# Fireplace_Control.net
KiCad netlist of a schematic drawn in EAGLE
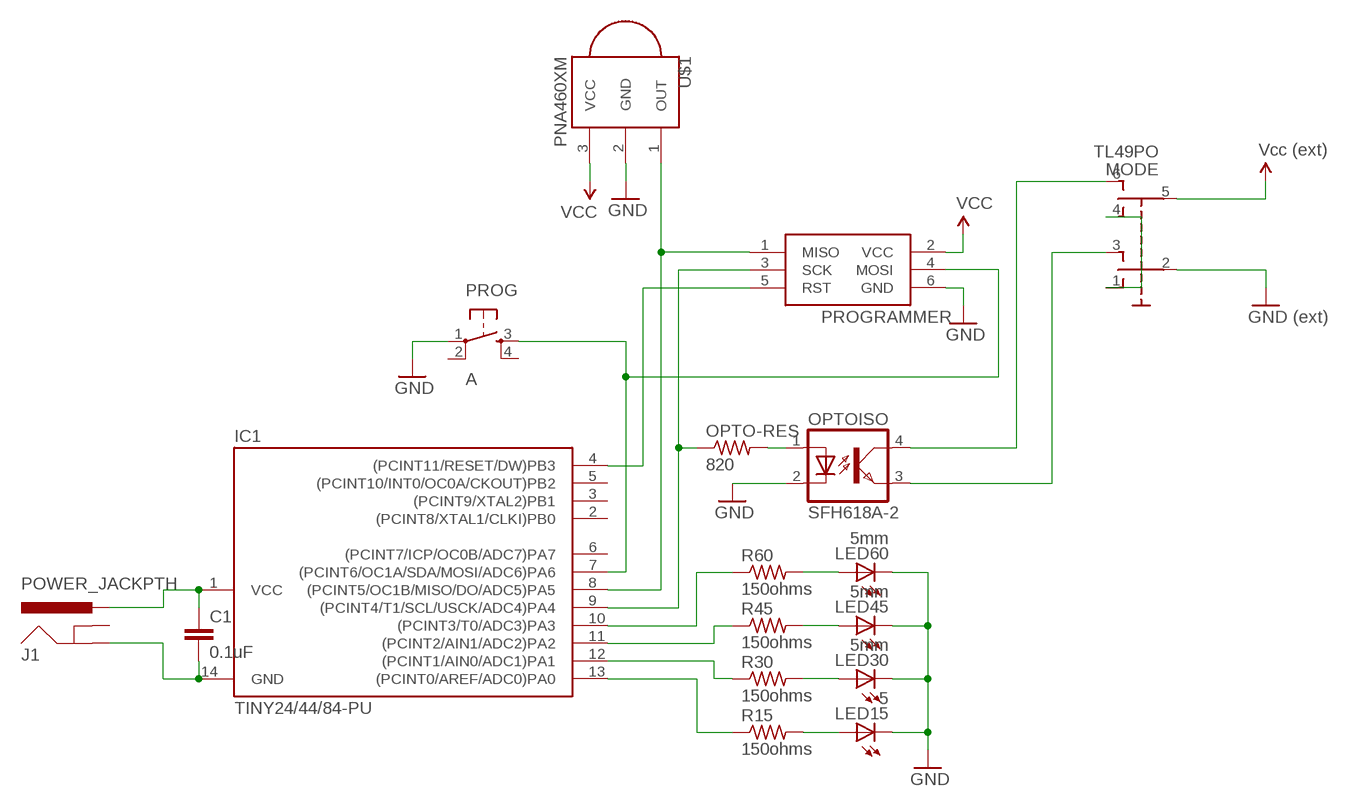
[diagram p0: schematic, sheet 1]

(export (version "E")
  (design (tool "Eeschema 10.0.6"))
  (components
    (comp (ref "C1")
      (value "0.1uF")
      (footprint "eagle-import:CAP-PTH-SMALL-KIT")
      (libsource (lib "eagle-import") (part "CAPKIT"))
    )
    (comp (ref "IC1")
      (value "TINY24/44/84-PU")
      (footprint "eagle-import:DIL14")
      (libsource (lib "eagle-import") (part "TINY24/44/84-PU"))
    )
    (comp (ref "J1")
      (value "POWER_JACKPTH")
      (footprint "eagle-import:POWER_JACK_PTH")
      (libsource (lib "eagle-import") (part "POWER_JACKPTH"))
    )
    (comp (ref "LED15")
      (value "5")
      (footprint "eagle-import:LED3MM")
      (libsource (lib "eagle-import") (part "LED3MM"))
    )
    (comp (ref "LED30")
      (value "5mm")
      (footprint "eagle-import:LED3MM")
      (libsource (lib "eagle-import") (part "LED3MM"))
    )
    (comp (ref "LED45")
      (value "5mm")
      (footprint "eagle-import:LED3MM")
      (libsource (lib "eagle-import") (part "LED3MM"))
    )
    (comp (ref "LED60")
      (value "5mm")
      (footprint "eagle-import:LED3MM")
      (libsource (lib "eagle-import") (part "LED3MM"))
    )
    (comp (ref "MODE")
      (value "TL49PO")
      (footprint "eagle-import:TL4XPO")
      (libsource (lib "eagle-import") (part "TL49PO"))
    )
    (comp (ref "OPTO-RES")
      (value "820")
      (footprint "eagle-import:0411_15")
      (libsource (lib "eagle-import") (part "R-US_0411/15"))
    )
    (comp (ref "OPTOISO")
      (value "SFH618A-2")
      (footprint "eagle-import:DIP4")
      (fields (field (name "MF") "VISHAY/TELEFUNKEN"))
      (libsource (lib "eagle-import") (part "SFH618?A-2"))
    )
    (comp (ref "PROG")
      (value "A")
      (footprint "eagle-import:TACTILE-PTH")
      (libsource (lib "eagle-import") (part "TAC_SWITCHPTH"))
    )
    (comp (ref "PROGRAMMER")
      (value "AVRISP-6")
      (footprint "eagle-import:AVRISP")
      (libsource (lib "eagle-import") (part "AVRISP-6"))
    )
    (comp (ref "R15")
      (value "150ohms")
      (footprint "eagle-import:0411_15")
      (libsource (lib "eagle-import") (part "R-US_0411/15"))
    )
    (comp (ref "R30")
      (value "150ohms")
      (footprint "eagle-import:0411_15")
      (libsource (lib "eagle-import") (part "R-US_0411/15"))
    )
    (comp (ref "R45")
      (value "150ohms")
      (footprint "eagle-import:0411_15")
      (libsource (lib "eagle-import") (part "R-US_0411/15"))
    )
    (comp (ref "R60")
      (value "150ohms")
      (footprint "eagle-import:0411_15")
      (libsource (lib "eagle-import") (part "R-US_0411/15"))
    )
    (comp (ref "U$1")
      (value "PNA460XM")
      (footprint "eagle-import:PNA460XM")
      (libsource (lib "eagle-import") (part "PNA460XM"))
    )
  )
  (nets
    (net (code "1") (name "GND") (class "Default")
      (node (ref "C1") (pin "2") (pinfunction "2_2") (pintype "passive"))
      (node (ref "IC1") (pin "14") (pinfunction "GND_14") (pintype "power_in"))
      (node (ref "J1") (pin "GND") (pinfunction "GND_GND") (pintype "bidirectional"))
      (node (ref "LED15") (pin "K") (pinfunction "C_K") (pintype "passive"))
      (node (ref "LED30") (pin "K") (pinfunction "C_K") (pintype "passive"))
      (node (ref "LED45") (pin "K") (pinfunction "C_K") (pintype "passive"))
      (node (ref "LED60") (pin "K") (pinfunction "C_K") (pintype "passive"))
      (node (ref "MODE") (pin "2") (pinfunction "P_2") (pintype "passive"))
      (node (ref "OPTOISO") (pin "2") (pinfunction "C_2") (pintype "passive"))
      (node (ref "PROG") (pin "1") (pinfunction "1_1") (pintype "passive"))
      (node (ref "PROGRAMMER") (pin "6") (pinfunction "GND_6") (pintype "power_in"))
      (node (ref "U$1") (pin "2") (pinfunction "GND_2") (pintype "power_in"))
    )
    (net (code "2") (name "Net-(IC1-(PCINT0{slash}AREF{slash}ADC0)PA0)") (class "Default")
      (node (ref "IC1") (pin "13") (pinfunction "(PCINT0/AREF/ADC0)PA0_13") (pintype "bidirectional"))
      (node (ref "R15") (pin "1") (pinfunction "1_1") (pintype "passive"))
    )
    (net (code "3") (name "Net-(IC1-(PCINT1{slash}AIN0{slash}ADC1)PA1)") (class "Default")
      (node (ref "IC1") (pin "12") (pinfunction "(PCINT1/AIN0/ADC1)PA1_12") (pintype "bidirectional"))
      (node (ref "R30") (pin "1") (pinfunction "1_1") (pintype "passive"))
    )
    (net (code "4") (name "Net-(IC1-(PCINT2{slash}AIN1{slash}ADC2)PA2)") (class "Default")
      (node (ref "IC1") (pin "11") (pinfunction "(PCINT2/AIN1/ADC2)PA2_11") (pintype "bidirectional"))
      (node (ref "R45") (pin "1") (pinfunction "1_1") (pintype "passive"))
    )
    (net (code "5") (name "Net-(IC1-(PCINT3{slash}T0{slash}ADC3)PA3)") (class "Default")
      (node (ref "IC1") (pin "10") (pinfunction "(PCINT3/T0/ADC3)PA3_10") (pintype "bidirectional"))
      (node (ref "R60") (pin "1") (pinfunction "1_1") (pintype "passive"))
    )
    (net (code "6") (name "Net-(IC1-(PCINT4{slash}T1{slash}SCL{slash}USCK{slash}ADC4)PA4)") (class "Default")
      (node (ref "IC1") (pin "9") (pinfunction "(PCINT4/T1/SCL/USCK/ADC4)PA4_9") (pintype "bidirectional"))
      (node (ref "OPTO-RES") (pin "1") (pinfunction "1_1") (pintype "passive"))
      (node (ref "PROGRAMMER") (pin "3") (pinfunction "SCK_3") (pintype "output"))
    )
    (net (code "7") (name "Net-(IC1-(PCINT5{slash}OC1B{slash}MISO{slash}DO{slash}ADC5)PA5)") (class "Default")
      (node (ref "IC1") (pin "8") (pinfunction "(PCINT5/OC1B/MISO/DO/ADC5)PA5_8") (pintype "bidirectional"))
      (node (ref "PROGRAMMER") (pin "1") (pinfunction "MISO_1") (pintype "input"))
      (node (ref "U$1") (pin "1") (pinfunction "OUT_1") (pintype "output"))
    )
    (net (code "8") (name "Net-(IC1-(PCINT6{slash}OC1A{slash}SDA{slash}MOSI{slash}ADC6)PA6)") (class "Default")
      (node (ref "IC1") (pin "7") (pinfunction "(PCINT6/OC1A/SDA/MOSI/ADC6)PA6_7") (pintype "bidirectional"))
      (node (ref "PROG") (pin "3") (pinfunction "3_3") (pintype "passive"))
      (node (ref "PROGRAMMER") (pin "4") (pinfunction "MOSI_4") (pintype "output"))
    )
    (net (code "9") (name "Net-(IC1-(PCINT11{slash}RESET{slash}DW)PB3)") (class "Default")
      (node (ref "IC1") (pin "4") (pinfunction "(PCINT11/RESET/DW)PB3_4") (pintype "bidirectional"))
      (node (ref "PROGRAMMER") (pin "5") (pinfunction "RST_5") (pintype "output"))
    )
    (net (code "10") (name "Net-(LED15-PadA)") (class "Default")
      (node (ref "LED15") (pin "A") (pinfunction "A_A") (pintype "passive"))
      (node (ref "R15") (pin "2") (pinfunction "2_2") (pintype "passive"))
    )
    (net (code "11") (name "Net-(LED30-PadA)") (class "Default")
      (node (ref "LED30") (pin "A") (pinfunction "A_A") (pintype "passive"))
      (node (ref "R30") (pin "2") (pinfunction "2_2") (pintype "passive"))
    )
    (net (code "12") (name "Net-(LED45-PadA)") (class "Default")
      (node (ref "LED45") (pin "A") (pinfunction "A_A") (pintype "passive"))
      (node (ref "R45") (pin "2") (pinfunction "2_2") (pintype "passive"))
    )
    (net (code "13") (name "Net-(LED60-PadA)") (class "Default")
      (node (ref "LED60") (pin "A") (pinfunction "A_A") (pintype "passive"))
      (node (ref "R60") (pin "2") (pinfunction "2_2") (pintype "passive"))
    )
    (net (code "14") (name "Net-(MODE-O)") (class "Default")
      (node (ref "MODE") (pin "1") (pinfunction "O_1") (pintype "passive"))
      (node (ref "MODE") (pin "4") (pinfunction "O1_4") (pintype "passive"))
    )
    (net (code "15") (name "Net-(MODE-S)") (class "Default")
      (node (ref "MODE") (pin "3") (pinfunction "S_3") (pintype "passive"))
      (node (ref "OPTOISO") (pin "3") (pinfunction "EMIT_3") (pintype "passive"))
    )
    (net (code "16") (name "Net-(MODE-S1)") (class "Default")
      (node (ref "MODE") (pin "6") (pinfunction "S1_6") (pintype "passive"))
      (node (ref "OPTOISO") (pin "4") (pinfunction "COL_4") (pintype "passive"))
    )
    (net (code "17") (name "Net-(OPTOISO-A)") (class "Default")
      (node (ref "OPTO-RES") (pin "2") (pinfunction "2_2") (pintype "passive"))
      (node (ref "OPTOISO") (pin "1") (pinfunction "A_1") (pintype "passive"))
    )
    (net (code "18") (name "VCC") (class "Default")
      (node (ref "C1") (pin "1") (pinfunction "1_1") (pintype "passive"))
      (node (ref "IC1") (pin "1") (pinfunction "VCC_1") (pintype "power_in"))
      (node (ref "J1") (pin "PWR") (pinfunction "PWR_PWR") (pintype "bidirectional"))
      (node (ref "MODE") (pin "5") (pinfunction "P1_5") (pintype "passive"))
      (node (ref "PROGRAMMER") (pin "2") (pinfunction "VCC_2") (pintype "power_in"))
      (node (ref "U$1") (pin "3") (pinfunction "VCC_3") (pintype "power_in"))
    )
    (net (code "19") (name "unconnected-(IC1-(PCINT7{slash}ICP{slash}OC0B{slash}ADC7)PA7-Pad6)") (class "Default")
      (node (ref "IC1") (pin "6") (pinfunction "(PCINT7/ICP/OC0B/ADC7)PA7_6") (pintype "bidirectional"))
    )
    (net (code "20") (name "unconnected-(IC1-(PCINT8{slash}XTAL1{slash}CLKI)PB0-Pad2)") (class "Default")
      (node (ref "IC1") (pin "2") (pinfunction "(PCINT8/XTAL1/CLKI)PB0_2") (pintype "bidirectional"))
    )
    (net (code "21") (name "unconnected-(IC1-(PCINT9{slash}XTAL2)PB1-Pad3)") (class "Default")
      (node (ref "IC1") (pin "3") (pinfunction "(PCINT9/XTAL2)PB1_3") (pintype "bidirectional"))
    )
    (net (code "22") (name "unconnected-(IC1-(PCINT10{slash}INT0{slash}OC0A{slash}CKOUT)PB2-Pad5)") (class "Default")
      (node (ref "IC1") (pin "5") (pinfunction "(PCINT10/INT0/OC0A/CKOUT)PB2_5") (pintype "bidirectional"))
    )
    (net (code "23") (name "unconnected-(J1-PadGNDBREAK)") (class "Default")
      (node (ref "J1") (pin "GNDBREAK") (pinfunction "GNDBREAK_GNDBREAK") (pintype "bidirectional"))
    )
    (net (code "24") (name "unconnected-(PROG-Pad2)") (class "Default")
      (node (ref "PROG") (pin "2") (pinfunction "2_2") (pintype "passive"))
    )
    (net (code "25") (name "unconnected-(PROG-Pad4)") (class "Default")
      (node (ref "PROG") (pin "4") (pinfunction "4_4") (pintype "passive"))
    )
  )
)
